# IndAlarmSe1.net
KiCad netlist of a schematic drawn in Altium Designer
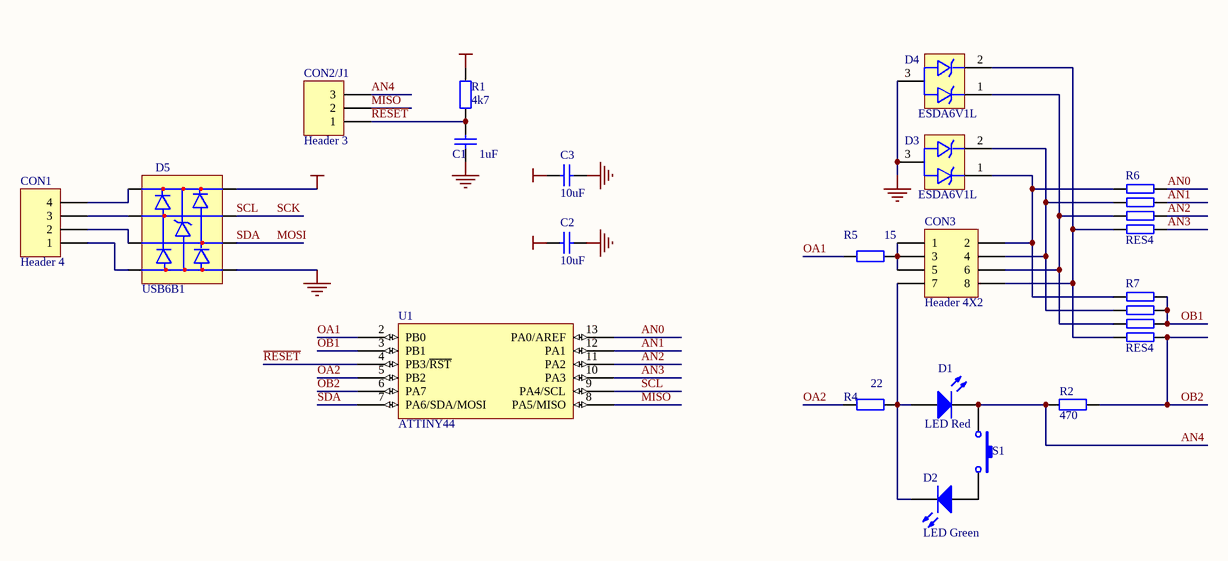
[diagram p0: IndAlarmSe1.SchDoc]

(export (version "E")
  (design (tool "Eeschema 10.0.6"))
  (components
    (comp (ref "C1")
      (value "1uF")
      (footprint "CC1608-0603")
      (description "Capacitor (Semiconductor SIM Model)")
      (fields (field (name "Comment") "Cap Semi") (field (name "PUBLISHER") "Altium Limited"))
      (libsource (lib "Miscellaneous Devices") (part "Cap Semi"))
    )
    (comp (ref "C2")
      (value "10uF")
      (footprint "CC3216-1206")
      (description "Capacitor (Semiconductor SIM Model)")
      (fields (field (name "Comment") "Cap Semi") (field (name "PUBLISHER") "Altium Limited"))
      (libsource (lib "Miscellaneous Devices") (part "Cap Semi"))
    )
    (comp (ref "C3")
      (value "10uF")
      (footprint "CC3216-1206")
      (description "Capacitor (Semiconductor SIM Model)")
      (fields (field (name "Comment") "Cap Semi") (field (name "PUBLISHER") "Altium Limited"))
      (libsource (lib "Miscellaneous Devices") (part "Cap Semi"))
    )
    (comp (ref "CON1")
      (value "Header 4")
      (footprint "4MM2")
      (description "Header, 4-Pin")
      (fields (field (name "PUBLISHER") "Altium Limited"))
      (libsource (lib "Miscellaneous Connectors") (part "Header 4"))
    )
    (comp (ref "CON2/J1")
      (value "Header 3")
      (footprint "3MM2L")
      (description "Header, 3-Pin")
      (fields (field (name "PUBLISHER") "Altium Limited"))
      (libsource (lib "Miscellaneous Connectors") (part "Header 3"))
    )
    (comp (ref "CON3")
      (value "Header 4X2")
      (footprint "4X2MM2")
      (description "Header, 4-Pin, Dual row")
      (fields (field (name "PUBLISHER") "Altium Limited"))
      (libsource (lib "Miscellaneous Connectors") (part "Header 4X2"))
    )
    (comp (ref "D1")
      (value "LED Red")
      (footprint "myLIB:LED3MM")
      (description "Typical BLUE SiC LED")
      (fields (field (name "PUBLISHER") "Altium Limited"))
      (libsource (lib "Miscellaneous Devices") (part "LED3"))
    )
    (comp (ref "D2")
      (value "LED Green")
      (footprint "myLIB:LED3MM")
      (description "Typical BLUE SiC LED")
      (fields (field (name "PUBLISHER") "Altium Limited"))
      (libsource (lib "Miscellaneous Devices") (part "LED3"))
    )
    (comp (ref "D3")
      (value "ESDA6V1L")
      (footprint "SO-G3/C2.5")
      (description "DUAL TRANSIL ARRAY\r\nFOR ESD PROTECTION")
      (libsource (lib "mySCHLIB") (part "ESDA6V1L"))
    )
    (comp (ref "D4")
      (value "ESDA6V1L")
      (footprint "SO-G3/C2.5")
      (description "DUAL TRANSIL ARRAY\r\nFOR ESD PROTECTION")
      (libsource (lib "mySCHLIB") (part "ESDA6V1L"))
    )
    (comp (ref "D5") (value "USB6B1") (footprint "NSO8") (libsource (lib "mySCHLIB") (part "USB6B1")))
    (comp (ref "R1")
      (value "4k7")
      (footprint "CR1608-0603")
      (description "Semiconductor Resistor")
      (fields (field (name "Comment") "Res Semi") (field (name "PUBLISHER") "Altium Limited"))
      (libsource (lib "") (part "Res Semi_2"))
    )
    (comp (ref "R2")
      (value "470")
      (footprint "CR1608-0603")
      (description "Semiconductor Resistor")
      (fields (field (name "Comment") "Res Semi") (field (name "PUBLISHER") "Altium Limited"))
      (libsource (lib "") (part "Res Semi_1"))
    )
    (comp (ref "R4")
      (value "22")
      (footprint "CR1608-0603")
      (description "Semiconductor Resistor")
      (fields (field (name "Comment") "Res Semi") (field (name "PUBLISHER") "Altium Limited"))
      (libsource (lib "Miscellaneous Devices") (part "Res Semi"))
    )
    (comp (ref "R5")
      (value "15")
      (footprint "CR1608-0603")
      (description "Semiconductor Resistor")
      (fields (field (name "Comment") "Res Semi") (field (name "PUBLISHER") "Altium Limited"))
      (libsource (lib "Miscellaneous Devices") (part "Res Semi"))
    )
    (comp (ref "R6") (value "RES4") (footprint "YC164") (libsource (lib "mySCHLIB") (part "RES4")))
    (comp (ref "R7") (value "RES4") (footprint "YC164") (libsource (lib "mySCHLIB") (part "RES4")))
    (comp (ref "S1")
      (value "SW-PB")
      (footprint "myLIB:SPPB512300")
      (description "Switch")
      (fields (field (name "PUBLISHER") "Altium Limited"))
      (libsource (lib "Miscellaneous Devices") (part "SW-PB"))
    )
    (comp (ref "U1") (value "ATTINY44") (footprint "SO-G14") (libsource (lib "Schlib1") (part "ATTINY44")))
  )
  (nets
    (net (code "1") (name "/AN0") (class "Default")
      (node (ref "R6") (pin "8") (pinfunction "6_8") (pintype "passive"))
      (node (ref "U1") (pin "13") (pinfunction "PA0/AREF_13") (pintype "bidirectional"))
    )
    (net (code "2") (name "/AN1") (class "Default")
      (node (ref "R6") (pin "7") (pinfunction "7_7") (pintype "passive"))
      (node (ref "U1") (pin "12") (pinfunction "PA1_12") (pintype "bidirectional"))
    )
    (net (code "3") (name "/AN2") (class "Default")
      (node (ref "R6") (pin "6") (pinfunction "6_6") (pintype "passive"))
      (node (ref "U1") (pin "11") (pinfunction "PA2_11") (pintype "bidirectional"))
    )
    (net (code "4") (name "/AN3") (class "Default")
      (node (ref "R6") (pin "5") (pinfunction "5_5") (pintype "passive"))
      (node (ref "U1") (pin "10") (pinfunction "PA3_10") (pintype "bidirectional"))
    )
    (net (code "5") (name "/AN4") (class "Default")
      (node (ref "CON2/J1") (pin "3") (pinfunction "3_3") (pintype "passive"))
      (node (ref "D1") (pin "2") (pinfunction "K_2") (pintype "passive"))
      (node (ref "R2") (pin "2") (pinfunction "2_2") (pintype "passive"))
      (node (ref "S1") (pin "1") (pinfunction "1_1") (pintype "passive"))
    )
    (net (code "6") (name "/MISO") (class "Default")
      (node (ref "CON2/J1") (pin "2") (pinfunction "2_2") (pintype "passive"))
      (node (ref "U1") (pin "8") (pinfunction "PA5/MISO_8") (pintype "bidirectional"))
    )
    (net (code "7") (name "/MOSI") (class "Default")
      (node (ref "D5") (pin "6") (pinfunction "I/O2_6") (pintype "passive"))
      (node (ref "U1") (pin "7") (pinfunction "PA6/SDA/MOSI_7") (pintype "bidirectional"))
    )
    (net (code "8") (name "/OA1") (class "Default")
      (node (ref "R5") (pin "1") (pinfunction "1_1") (pintype "passive"))
      (node (ref "U1") (pin "2") (pinfunction "PB0_2") (pintype "bidirectional"))
    )
    (net (code "9") (name "/OA2") (class "Default")
      (node (ref "R4") (pin "1") (pinfunction "1_1") (pintype "passive"))
      (node (ref "U1") (pin "5") (pinfunction "PB2_5") (pintype "bidirectional"))
    )
    (net (code "10") (name "/OB1") (class "Default")
      (node (ref "R7") (pin "6") (pinfunction "6_6") (pintype "passive"))
      (node (ref "R7") (pin "7") (pinfunction "7_7") (pintype "passive"))
      (node (ref "R7") (pin "8") (pinfunction "6_8") (pintype "passive"))
      (node (ref "U1") (pin "3") (pinfunction "PB1_3") (pintype "bidirectional"))
    )
    (net (code "11") (name "/OB2") (class "Default")
      (node (ref "R2") (pin "1") (pinfunction "1_1") (pintype "passive"))
      (node (ref "R7") (pin "5") (pinfunction "5_5") (pintype "passive"))
      (node (ref "U1") (pin "6") (pinfunction "PA7_6") (pintype "bidirectional"))
    )
    (net (code "12") (name "/SCK") (class "Default")
      (node (ref "D5") (pin "7") (pinfunction "I/O1_7") (pintype "passive"))
      (node (ref "U1") (pin "9") (pinfunction "PA4/SCL_9") (pintype "bidirectional"))
    )
    (net (code "13") (name "/~{RESET}") (class "Default")
      (node (ref "C1") (pin "2") (pinfunction "2_2") (pintype "passive"))
      (node (ref "CON2/J1") (pin "1") (pinfunction "1_1") (pintype "passive"))
      (node (ref "R1") (pin "2") (pinfunction "2_2") (pintype "passive"))
      (node (ref "U1") (pin "4") (pinfunction "PB3/~{RST}_4") (pintype "bidirectional"))
    )
    (net (code "14") (name "GND") (class "Default")
      (node (ref "C1") (pin "1") (pinfunction "1_1") (pintype "passive"))
      (node (ref "C2") (pin "1") (pinfunction "1_1") (pintype "passive"))
      (node (ref "C3") (pin "1") (pinfunction "1_1") (pintype "passive"))
      (node (ref "D3") (pin "3") (pinfunction "3_3") (pintype "passive"))
      (node (ref "D4") (pin "3") (pinfunction "3_3") (pintype "passive"))
      (node (ref "D5") (pin "5") (pinfunction "GND_5") (pintype "power_in"))
      (node (ref "U1") (pin "14") (pinfunction "GND_14") (pintype "power_in"))
    )
    (net (code "15") (name "Net-(CON1-Pad1)") (class "Default")
      (node (ref "CON1") (pin "1") (pinfunction "1_1") (pintype "passive"))
      (node (ref "D5") (pin "4") (pinfunction "GND_4") (pintype "power_in"))
    )
    (net (code "16") (name "Net-(CON1-Pad2)") (class "Default")
      (node (ref "CON1") (pin "2") (pinfunction "2_2") (pintype "passive"))
      (node (ref "D5") (pin "3") (pinfunction "I/O2_3") (pintype "passive"))
    )
    (net (code "17") (name "Net-(CON1-Pad3)") (class "Default")
      (node (ref "CON1") (pin "3") (pinfunction "3_3") (pintype "passive"))
      (node (ref "D5") (pin "2") (pinfunction "I/O1_2") (pintype "passive"))
    )
    (net (code "18") (name "Net-(CON1-Pad4)") (class "Default")
      (node (ref "CON1") (pin "4") (pinfunction "4_4") (pintype "passive"))
      (node (ref "D5") (pin "1") (pinfunction "VCC_1") (pintype "power_in"))
    )
    (net (code "19") (name "Net-(CON3-Pad1)") (class "Default")
      (node (ref "CON3") (pin "1") (pinfunction "1_1") (pintype "passive"))
      (node (ref "CON3") (pin "3") (pinfunction "3_3") (pintype "passive"))
      (node (ref "CON3") (pin "5") (pinfunction "5_5") (pintype "passive"))
      (node (ref "R5") (pin "2") (pinfunction "2_2") (pintype "passive"))
    )
    (net (code "20") (name "Net-(CON3-Pad2)") (class "Default")
      (node (ref "CON3") (pin "2") (pinfunction "2_2") (pintype "passive"))
      (node (ref "D3") (pin "1") (pinfunction "1_1") (pintype "passive"))
      (node (ref "R6") (pin "1") (pinfunction "1_1") (pintype "passive"))
      (node (ref "R7") (pin "1") (pinfunction "1_1") (pintype "passive"))
    )
    (net (code "21") (name "Net-(CON3-Pad4)") (class "Default")
      (node (ref "CON3") (pin "4") (pinfunction "4_4") (pintype "passive"))
      (node (ref "D3") (pin "2") (pinfunction "2_2") (pintype "passive"))
      (node (ref "R6") (pin "2") (pinfunction "2_2") (pintype "passive"))
      (node (ref "R7") (pin "2") (pinfunction "2_2") (pintype "passive"))
    )
    (net (code "22") (name "Net-(CON3-Pad6)") (class "Default")
      (node (ref "CON3") (pin "6") (pinfunction "6_6") (pintype "passive"))
      (node (ref "D4") (pin "1") (pinfunction "1_1") (pintype "passive"))
      (node (ref "R6") (pin "3") (pinfunction "3_3") (pintype "passive"))
      (node (ref "R7") (pin "3") (pinfunction "3_3") (pintype "passive"))
    )
    (net (code "23") (name "Net-(CON3-Pad8)") (class "Default")
      (node (ref "CON3") (pin "8") (pinfunction "8_8") (pintype "passive"))
      (node (ref "D4") (pin "2") (pinfunction "2_2") (pintype "passive"))
      (node (ref "R6") (pin "4") (pinfunction "4_4") (pintype "passive"))
      (node (ref "R7") (pin "4") (pinfunction "4_4") (pintype "passive"))
    )
    (net (code "24") (name "Net-(D1-A)") (class "Default")
      (node (ref "CON3") (pin "7") (pinfunction "7_7") (pintype "passive"))
      (node (ref "D1") (pin "1") (pinfunction "A_1") (pintype "passive"))
      (node (ref "D2") (pin "2") (pinfunction "K_2") (pintype "passive"))
      (node (ref "R4") (pin "2") (pinfunction "2_2") (pintype "passive"))
    )
    (net (code "25") (name "Net-(D2-A)") (class "Default")
      (node (ref "D2") (pin "1") (pinfunction "A_1") (pintype "passive"))
      (node (ref "S1") (pin "2") (pinfunction "2_2") (pintype "passive"))
    )
    (net (code "26") (name "VCC") (class "Default")
      (node (ref "C2") (pin "2") (pinfunction "2_2") (pintype "passive"))
      (node (ref "C3") (pin "2") (pinfunction "2_2") (pintype "passive"))
      (node (ref "D5") (pin "8") (pinfunction "VCC_8") (pintype "power_in"))
      (node (ref "R1") (pin "1") (pinfunction "1_1") (pintype "passive"))
      (node (ref "U1") (pin "1") (pinfunction "VCC_1") (pintype "power_in"))
    )
  )
)
